# Main.net
KiCad netlist of a schematic drawn in Altium Designer
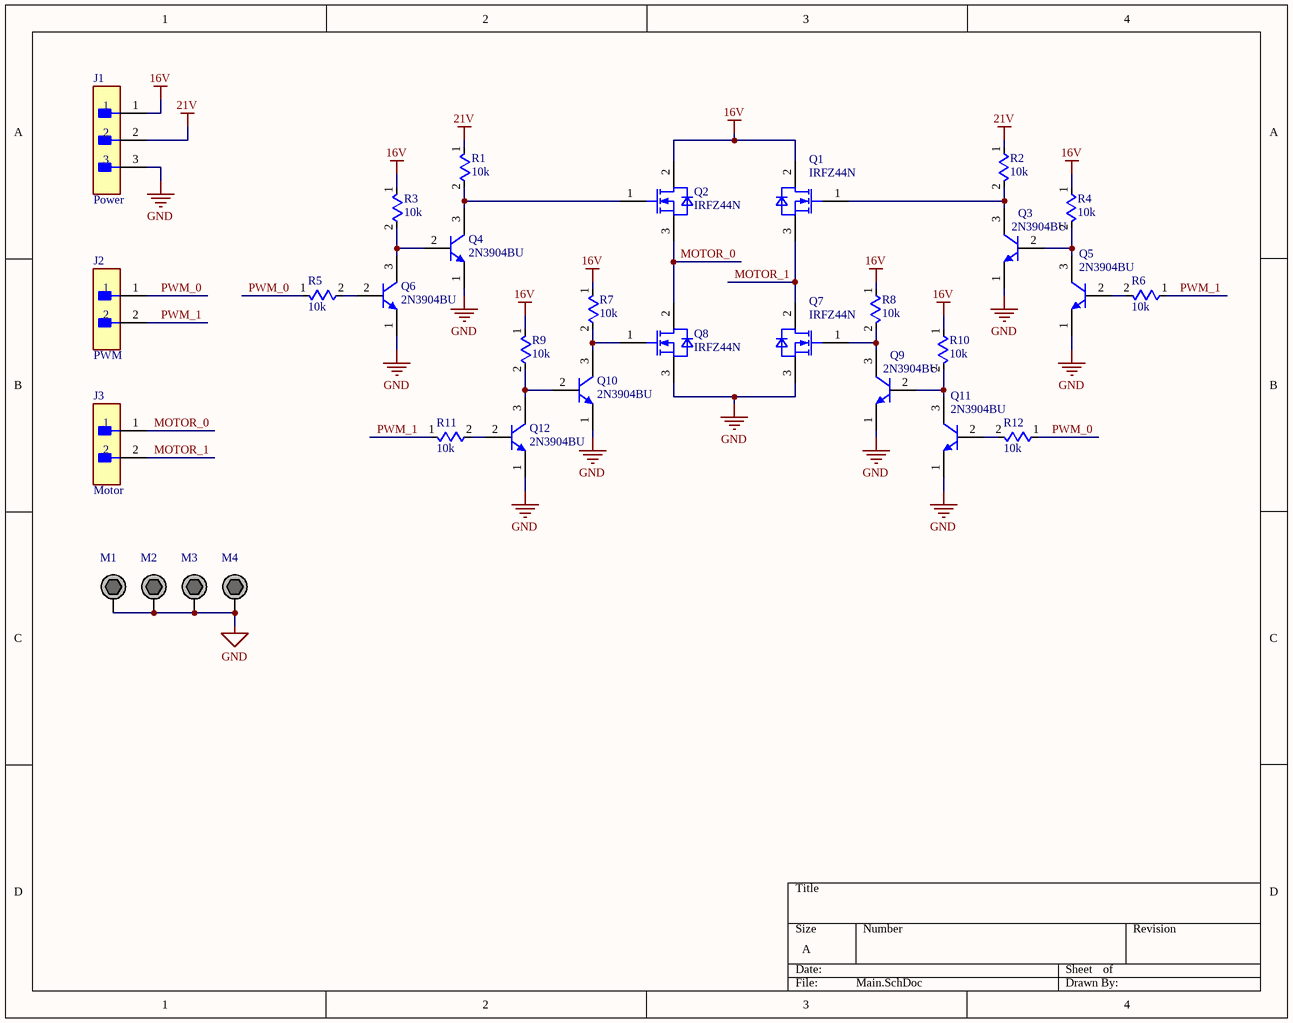
[diagram p0: Main.SchDoc]

(export (version "E")
  (design (tool "Eeschema 10.0.6"))
  (components
    (comp (ref "J1")
      (value "Power")
      (footprint "FP-B3B-XH-A_LF_SN-MFG")
      (description "CONN HEADER VERT 3POS 2.5MM")
      (libsource (lib "Altium Content Vault") (part "0d3f023dd272f625e17a2be33dea85f"))
    )
    (comp (ref "J2")
      (value "PWM")
      (footprint "FP-B2B-XH-A_LF_SN-MFG")
      (description "CONN HEADER VERT 2POS 2.5MM")
      (libsource (lib "Altium Content Vault") (part "3bc925449376181038e59eaffc5286c"))
    )
    (comp (ref "J3")
      (value "Motor")
      (footprint "FP-B2B-XH-A_LF_SN-MFG")
      (description "CONN HEADER VERT 2POS 2.5MM")
      (libsource (lib "Altium Content Vault") (part "3bc925449376181038e59eaffc5286c"))
    )
    (comp (ref "M1")
      (value "M3 Mounting Hole Plated")
      (footprint "M3 Screw Hole - Plated")
      (fields (field (name "SOURCE") "UBC Formula Electric.SchLib"))
      (libsource (lib "UBC Formula Electric") (part "Symbol"))
    )
    (comp (ref "M2")
      (value "M3 Mounting Hole Plated")
      (footprint "M3 Screw Hole - Plated")
      (fields (field (name "SOURCE") "UBC Formula Electric.SchLib"))
      (libsource (lib "UBC Formula Electric") (part "Symbol"))
    )
    (comp (ref "M3")
      (value "M3 Mounting Hole Plated")
      (footprint "M3 Screw Hole - Plated")
      (fields (field (name "SOURCE") "UBC Formula Electric.SchLib"))
      (libsource (lib "UBC Formula Electric") (part "Symbol"))
    )
    (comp (ref "M4")
      (value "M3 Mounting Hole Plated")
      (footprint "M3 Screw Hole - Plated")
      (fields (field (name "SOURCE") "UBC Formula Electric.SchLib"))
      (libsource (lib "UBC Formula Electric") (part "Symbol"))
    )
    (comp (ref "Q1")
      (value "IRFZ44N")
      (footprint "MD_PcbLib:IFX-PG-TO220-3-904-1")
      (description "OptiMOS 3 Power-Transistor, VDS 100V")
      (fields (field (name "MANUFACTURER") "Infineon Technologies"))
      (libsource (lib "MD_Schlib") (part "IRFZ44N"))
    )
    (comp (ref "Q2")
      (value "IRFZ44N")
      (footprint "MD_PcbLib:IFX-PG-TO220-3-904-1")
      (description "OptiMOS 3 Power-Transistor, VDS 100V")
      (fields (field (name "MANUFACTURER") "Infineon Technologies"))
      (libsource (lib "MD_Schlib") (part "IRFZ44N"))
    )
    (comp (ref "Q3")
      (value "2N3904BU")
      (footprint "MD_PcbLib:2n3904")
      (description "NPN General-Purpose Amplifier, 40 V VCEO, 0.2 A, -55 to 150 degC, 2-Pin TO-92, RoHS, Bulk")
      (fields (field (name "MANUFACTURER") "FairchildSemiconductor"))
      (libsource (lib "MD_Schlib") (part "2n3904"))
    )
    (comp (ref "Q4")
      (value "2N3904BU")
      (footprint "MD_PcbLib:2n3904")
      (description "NPN General-Purpose Amplifier, 40 V VCEO, 0.2 A, -55 to 150 degC, 2-Pin TO-92, RoHS, Bulk")
      (fields (field (name "MANUFACTURER") "FairchildSemiconductor"))
      (libsource (lib "MD_Schlib") (part "2n3904"))
    )
    (comp (ref "Q5")
      (value "2N3904BU")
      (footprint "MD_PcbLib:2n3904")
      (description "NPN General-Purpose Amplifier, 40 V VCEO, 0.2 A, -55 to 150 degC, 2-Pin TO-92, RoHS, Bulk")
      (fields (field (name "MANUFACTURER") "FairchildSemiconductor"))
      (libsource (lib "MD_Schlib") (part "2n3904"))
    )
    (comp (ref "Q6")
      (value "2N3904BU")
      (footprint "MD_PcbLib:2n3904")
      (description "NPN General-Purpose Amplifier, 40 V VCEO, 0.2 A, -55 to 150 degC, 2-Pin TO-92, RoHS, Bulk")
      (fields (field (name "MANUFACTURER") "FairchildSemiconductor"))
      (libsource (lib "MD_Schlib") (part "2n3904"))
    )
    (comp (ref "Q7")
      (value "IRFZ44N")
      (footprint "MD_PcbLib:IFX-PG-TO220-3-904-1")
      (description "OptiMOS 3 Power-Transistor, VDS 100V")
      (fields (field (name "MANUFACTURER") "Infineon Technologies"))
      (libsource (lib "MD_Schlib") (part "IRFZ44N"))
    )
    (comp (ref "Q8")
      (value "IRFZ44N")
      (footprint "MD_PcbLib:IFX-PG-TO220-3-904-1")
      (description "OptiMOS 3 Power-Transistor, VDS 100V")
      (fields (field (name "MANUFACTURER") "Infineon Technologies"))
      (libsource (lib "MD_Schlib") (part "IRFZ44N"))
    )
    (comp (ref "Q9")
      (value "2N3904BU")
      (footprint "MD_PcbLib:2n3904")
      (description "NPN General-Purpose Amplifier, 40 V VCEO, 0.2 A, -55 to 150 degC, 2-Pin TO-92, RoHS, Bulk")
      (fields (field (name "MANUFACTURER") "FairchildSemiconductor"))
      (libsource (lib "MD_Schlib") (part "2n3904"))
    )
    (comp (ref "Q10")
      (value "2N3904BU")
      (footprint "MD_PcbLib:2n3904")
      (description "NPN General-Purpose Amplifier, 40 V VCEO, 0.2 A, -55 to 150 degC, 2-Pin TO-92, RoHS, Bulk")
      (fields (field (name "MANUFACTURER") "FairchildSemiconductor"))
      (libsource (lib "MD_Schlib") (part "2n3904"))
    )
    (comp (ref "Q11")
      (value "2N3904BU")
      (footprint "MD_PcbLib:2n3904")
      (description "NPN General-Purpose Amplifier, 40 V VCEO, 0.2 A, -55 to 150 degC, 2-Pin TO-92, RoHS, Bulk")
      (fields (field (name "MANUFACTURER") "FairchildSemiconductor"))
      (libsource (lib "MD_Schlib") (part "2n3904"))
    )
    (comp (ref "Q12")
      (value "2N3904BU")
      (footprint "MD_PcbLib:2n3904")
      (description "NPN General-Purpose Amplifier, 40 V VCEO, 0.2 A, -55 to 150 degC, 2-Pin TO-92, RoHS, Bulk")
      (fields (field (name "MANUFACTURER") "FairchildSemiconductor"))
      (libsource (lib "MD_Schlib") (part "2n3904"))
    )
    (comp (ref "R1")
      (value "10k")
      (footprint "MD_PcbLib:Axial 0.5")
      (libsource (lib "MD_Schlib") (part "RES_GENERIC"))
    )
    (comp (ref "R2")
      (value "10k")
      (footprint "MD_PcbLib:Axial 0.5")
      (libsource (lib "MD_Schlib") (part "RES_GENERIC"))
    )
    (comp (ref "R3")
      (value "10k")
      (footprint "MD_PcbLib:Axial 0.5")
      (libsource (lib "MD_Schlib") (part "RES_GENERIC"))
    )
    (comp (ref "R4")
      (value "10k")
      (footprint "MD_PcbLib:Axial 0.5")
      (libsource (lib "MD_Schlib") (part "RES_GENERIC"))
    )
    (comp (ref "R5")
      (value "10k")
      (footprint "MD_PcbLib:Axial 0.5")
      (libsource (lib "MD_Schlib") (part "RES_GENERIC"))
    )
    (comp (ref "R6")
      (value "10k")
      (footprint "MD_PcbLib:Axial 0.5")
      (libsource (lib "MD_Schlib") (part "RES_GENERIC"))
    )
    (comp (ref "R7")
      (value "10k")
      (footprint "MD_PcbLib:Axial 0.5")
      (libsource (lib "MD_Schlib") (part "RES_GENERIC"))
    )
    (comp (ref "R8")
      (value "10k")
      (footprint "MD_PcbLib:Axial 0.5")
      (libsource (lib "MD_Schlib") (part "RES_GENERIC"))
    )
    (comp (ref "R9")
      (value "10k")
      (footprint "MD_PcbLib:Axial 0.5")
      (libsource (lib "MD_Schlib") (part "RES_GENERIC"))
    )
    (comp (ref "R10")
      (value "10k")
      (footprint "MD_PcbLib:Axial 0.5")
      (libsource (lib "MD_Schlib") (part "RES_GENERIC"))
    )
    (comp (ref "R11")
      (value "10k")
      (footprint "MD_PcbLib:Axial 0.5")
      (libsource (lib "MD_Schlib") (part "RES_GENERIC"))
    )
    (comp (ref "R12")
      (value "10k")
      (footprint "MD_PcbLib:Axial 0.5")
      (libsource (lib "MD_Schlib") (part "RES_GENERIC"))
    )
  )
  (nets
    (net (code "1") (name "/MOTOR_0") (class "Default")
      (node (ref "J3") (pin "1") (pinfunction "1_1") (pintype "passive"))
      (node (ref "Q2") (pin "3") (pinfunction "SOURCE_3") (pintype "passive"))
      (node (ref "Q8") (pin "2") (pinfunction "DRAIN_2") (pintype "passive"))
    )
    (net (code "2") (name "/MOTOR_1") (class "Default")
      (node (ref "J3") (pin "2") (pinfunction "2_2") (pintype "passive"))
      (node (ref "Q1") (pin "3") (pinfunction "SOURCE_3") (pintype "passive"))
      (node (ref "Q7") (pin "2") (pinfunction "DRAIN_2") (pintype "passive"))
    )
    (net (code "3") (name "/PWM_0") (class "Default")
      (node (ref "J2") (pin "1") (pinfunction "1_1") (pintype "passive"))
      (node (ref "R12") (pin "1") (pintype "passive"))
      (node (ref "R5") (pin "1") (pintype "passive"))
    )
    (net (code "4") (name "/PWM_1") (class "Default")
      (node (ref "J2") (pin "2") (pinfunction "2_2") (pintype "passive"))
      (node (ref "R11") (pin "1") (pintype "passive"))
      (node (ref "R6") (pin "1") (pintype "passive"))
    )
    (net (code "5") (name "16V") (class "Default")
      (node (ref "J1") (pin "1") (pinfunction "1_1") (pintype "passive"))
      (node (ref "Q1") (pin "2") (pinfunction "DRAIN_2") (pintype "passive"))
      (node (ref "Q2") (pin "2") (pinfunction "DRAIN_2") (pintype "passive"))
      (node (ref "R10") (pin "1") (pintype "passive"))
      (node (ref "R3") (pin "1") (pintype "passive"))
      (node (ref "R4") (pin "1") (pintype "passive"))
      (node (ref "R7") (pin "1") (pintype "passive"))
      (node (ref "R8") (pin "1") (pintype "passive"))
      (node (ref "R9") (pin "1") (pintype "passive"))
    )
    (net (code "6") (name "21V") (class "Default")
      (node (ref "J1") (pin "2") (pinfunction "2_2") (pintype "passive"))
      (node (ref "R1") (pin "1") (pintype "passive"))
      (node (ref "R2") (pin "1") (pintype "passive"))
    )
    (net (code "7") (name "GND") (class "Default")
      (node (ref "J1") (pin "3") (pinfunction "3_3") (pintype "passive"))
      (node (ref "M1") (pin "1") (pinfunction "1_1") (pintype "passive"))
      (node (ref "M2") (pin "1") (pinfunction "1_1") (pintype "passive"))
      (node (ref "M3") (pin "1") (pinfunction "1_1") (pintype "passive"))
      (node (ref "M4") (pin "1") (pinfunction "1_1") (pintype "passive"))
      (node (ref "Q10") (pin "1") (pinfunction "E_1") (pintype "passive"))
      (node (ref "Q11") (pin "1") (pinfunction "E_1") (pintype "passive"))
      (node (ref "Q12") (pin "1") (pinfunction "E_1") (pintype "passive"))
      (node (ref "Q3") (pin "1") (pinfunction "E_1") (pintype "passive"))
      (node (ref "Q4") (pin "1") (pinfunction "E_1") (pintype "passive"))
      (node (ref "Q5") (pin "1") (pinfunction "E_1") (pintype "passive"))
      (node (ref "Q6") (pin "1") (pinfunction "E_1") (pintype "passive"))
      (node (ref "Q7") (pin "3") (pinfunction "SOURCE_3") (pintype "passive"))
      (node (ref "Q8") (pin "3") (pinfunction "SOURCE_3") (pintype "passive"))
      (node (ref "Q9") (pin "1") (pinfunction "E_1") (pintype "passive"))
    )
    (net (code "8") (name "Net-(Q1-GATE)") (class "Default")
      (node (ref "Q1") (pin "1") (pinfunction "GATE_1") (pintype "passive"))
      (node (ref "Q3") (pin "3") (pinfunction "C_3") (pintype "passive"))
      (node (ref "R2") (pin "2") (pintype "passive"))
    )
    (net (code "9") (name "Net-(Q2-GATE)") (class "Default")
      (node (ref "Q2") (pin "1") (pinfunction "GATE_1") (pintype "passive"))
      (node (ref "Q4") (pin "3") (pinfunction "C_3") (pintype "passive"))
      (node (ref "R1") (pin "2") (pintype "passive"))
    )
    (net (code "10") (name "Net-(Q3-B)") (class "Default")
      (node (ref "Q3") (pin "2") (pinfunction "B_2") (pintype "passive"))
      (node (ref "Q5") (pin "3") (pinfunction "C_3") (pintype "passive"))
      (node (ref "R4") (pin "2") (pintype "passive"))
    )
    (net (code "11") (name "Net-(Q4-B)") (class "Default")
      (node (ref "Q4") (pin "2") (pinfunction "B_2") (pintype "passive"))
      (node (ref "Q6") (pin "3") (pinfunction "C_3") (pintype "passive"))
      (node (ref "R3") (pin "2") (pintype "passive"))
    )
    (net (code "12") (name "Net-(Q5-B)") (class "Default")
      (node (ref "Q5") (pin "2") (pinfunction "B_2") (pintype "passive"))
      (node (ref "R6") (pin "2") (pintype "passive"))
    )
    (net (code "13") (name "Net-(Q6-B)") (class "Default")
      (node (ref "Q6") (pin "2") (pinfunction "B_2") (pintype "passive"))
      (node (ref "R5") (pin "2") (pintype "passive"))
    )
    (net (code "14") (name "Net-(Q7-GATE)") (class "Default")
      (node (ref "Q7") (pin "1") (pinfunction "GATE_1") (pintype "passive"))
      (node (ref "Q9") (pin "3") (pinfunction "C_3") (pintype "passive"))
      (node (ref "R8") (pin "2") (pintype "passive"))
    )
    (net (code "15") (name "Net-(Q10-B)") (class "Default")
      (node (ref "Q10") (pin "2") (pinfunction "B_2") (pintype "passive"))
      (node (ref "Q12") (pin "3") (pinfunction "C_3") (pintype "passive"))
      (node (ref "R9") (pin "2") (pintype "passive"))
    )
    (net (code "16") (name "Net-(Q10-C)") (class "Default")
      (node (ref "Q10") (pin "3") (pinfunction "C_3") (pintype "passive"))
      (node (ref "Q8") (pin "1") (pinfunction "GATE_1") (pintype "passive"))
      (node (ref "R7") (pin "2") (pintype "passive"))
    )
    (net (code "17") (name "Net-(Q11-B)") (class "Default")
      (node (ref "Q11") (pin "2") (pinfunction "B_2") (pintype "passive"))
      (node (ref "R12") (pin "2") (pintype "passive"))
    )
    (net (code "18") (name "Net-(Q11-C)") (class "Default")
      (node (ref "Q11") (pin "3") (pinfunction "C_3") (pintype "passive"))
      (node (ref "Q9") (pin "2") (pinfunction "B_2") (pintype "passive"))
      (node (ref "R10") (pin "2") (pintype "passive"))
    )
    (net (code "19") (name "Net-(Q12-B)") (class "Default")
      (node (ref "Q12") (pin "2") (pinfunction "B_2") (pintype "passive"))
      (node (ref "R11") (pin "2") (pintype "passive"))
    )
  )
)
